# 261105902xxxx-HW-V1_1.net
KiCad netlist of a schematic drawn in EAGLE
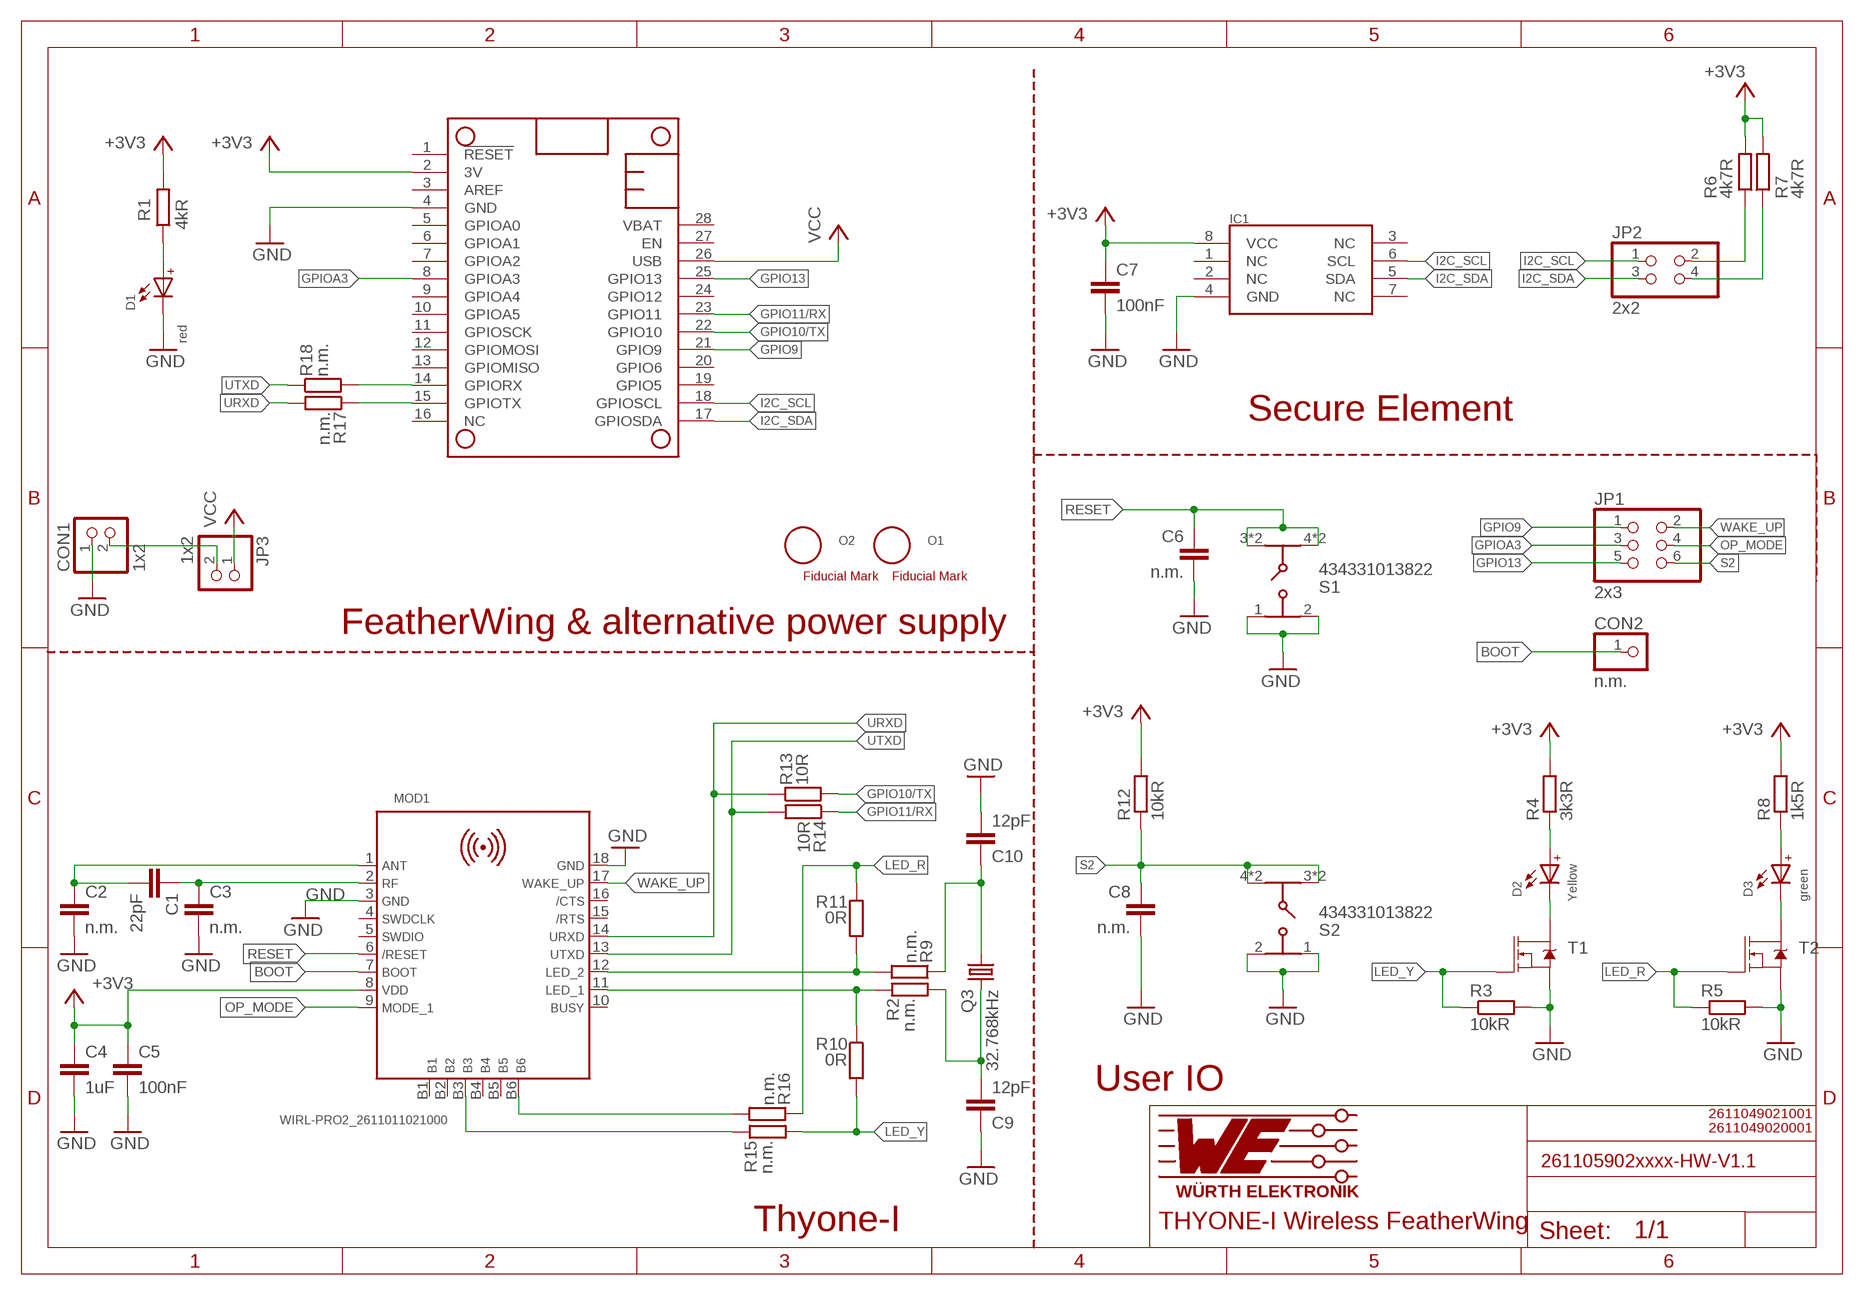
[diagram p0: schematic, sheet 1]

(export (version "E")
  (design (tool "Eeschema 10.0.6"))
  (components
    (comp (ref "C1")
      (value "22pF")
      (footprint "eagle-import:C0402_IPC")
      (fields (field (name "MANUFACTURER") "Samsung"))
      (libsource (lib "eagle-import") (part "rcl-amber_C0402_IPC22PF"))
    )
    (comp (ref "C2")
      (value "n.m.")
      (footprint "eagle-import:C0402_IPC")
      (fields (field (name "MANUFACTURER") "Würth Elektronik"))
      (libsource (lib "eagle-import") (part "C0402_IPC"))
    )
    (comp (ref "C3")
      (value "n.m.")
      (footprint "eagle-import:C0402_IPC")
      (fields (field (name "MANUFACTURER") "Würth Elektronik"))
      (libsource (lib "eagle-import") (part "C0402_IPC"))
    )
    (comp (ref "C4")
      (value "1uF")
      (footprint "eagle-import:C0402_IPC")
      (fields (field (name "MANUFACTURER") "Samsung"))
      (libsource (lib "eagle-import") (part "rcl-amber_C0402_IPC1UF"))
    )
    (comp (ref "C5")
      (value "100nF")
      (footprint "eagle-import:C0402_IPC")
      (fields (field (name "MANUFACTURER") "Yageo"))
      (libsource (lib "eagle-import") (part "rcl-amber_C0402_IPC100NF"))
    )
    (comp (ref "C6")
      (value "n.m.")
      (footprint "eagle-import:C0402_IPC")
      (fields (field (name "MANUFACTURER") "Würth Elektronik"))
      (libsource (lib "eagle-import") (part "C0402_IPC"))
    )
    (comp (ref "C7")
      (value "100nF")
      (footprint "eagle-import:C0402_IPC")
      (fields (field (name "MANUFACTURER") "Yageo"))
      (libsource (lib "eagle-import") (part "rcl-amber_C0402_IPC100NF"))
    )
    (comp (ref "C8")
      (value "n.m.")
      (footprint "eagle-import:C0402_IPC")
      (fields (field (name "MANUFACTURER") "Würth Elektronik"))
      (libsource (lib "eagle-import") (part "C0402_IPC"))
    )
    (comp (ref "C9")
      (value "12pF")
      (footprint "eagle-import:C0402_IPC")
      (fields (field (name "MANUFACTURER") "Yageo"))
      (libsource (lib "eagle-import") (part "C0402_IPC12PF"))
    )
    (comp (ref "C10")
      (value "12pF")
      (footprint "eagle-import:C0402_IPC")
      (fields (field (name "MANUFACTURER") "Yageo"))
      (libsource (lib "eagle-import") (part "C0402_IPC12PF"))
    )
    (comp (ref "CON1")
      (value "1x2")
      (footprint "eagle-import:1X02_R")
      (fields (field (name "MANUFACTURER") "Würth Elektronik"))
      (libsource (lib "eagle-import") (part "PINHD-1X2/R"))
    )
    (comp (ref "CON2")
      (value "n.m.")
      (footprint "eagle-import:1X01_R")
      (libsource (lib "eagle-import") (part "PINHD-1X1/R"))
    )
    (comp (ref "D1")
      (value "red")
      (footprint "eagle-import:WL-SMSW_1204_A")
      (fields (field (name "MANUFACTURER") "Würth Elektronik"))
      (libsource (lib "eagle-import") (part "WL-SMSW_1204_155124VS73200"))
    )
    (comp (ref "D2")
      (value "Yellow")
      (footprint "eagle-import:WL-SMSW_1204_A")
      (fields (field (name "MANUFACTURER") "Würth Elektronik"))
      (libsource (lib "eagle-import") (part "WL-SMSW_1204_155124YS73200"))
    )
    (comp (ref "D3")
      (value "green")
      (footprint "eagle-import:WL-SMSW_1204_A")
      (fields (field (name "MANUFACTURER") "Würth Elektronik"))
      (libsource (lib "eagle-import") (part "WL-SMSW_1204_155124VS73200"))
    )
    (comp (ref "IC1")
      (value "ATECC608A")
      (footprint "eagle-import:SOIC127P600X175-8N")
      (fields (field (name "MANUFACTURER") "microchip"))
      (libsource (lib "eagle-import") (part "ATECC608ASOIC8"))
    )
    (comp (ref "JP1")
      (value "2x3")
      (footprint "eagle-import:2X03")
      (fields (field (name "MANUFACTURER") "Würth Elektronik"))
      (libsource (lib "eagle-import") (part "PINHD-2X3"))
    )
    (comp (ref "JP2")
      (value "2x2")
      (footprint "eagle-import:2X02")
      (fields (field (name "MANUFACTURER") "Würth Elektronik"))
      (libsource (lib "eagle-import") (part "PINHD-2X2"))
    )
    (comp (ref "JP3")
      (value "1x2")
      (footprint "eagle-import:1X02_R")
      (fields (field (name "MANUFACTURER") "Würth Elektronik"))
      (libsource (lib "eagle-import") (part "PINHD-1X2/R"))
    )
    (comp (ref "MOD1")
      (value "WIRL-PRO2_2611011021000")
      (footprint "eagle-import:WIRL-PRO2_2611011021000")
      (fields (field (name "MANUFACTURER") "Würth Elektronik"))
      (libsource (lib "eagle-import") (part "WIRL-PRO2_2611011021000"))
    )
    (comp (ref "MS1")
      (value "header: 1 x 12 & 1 x 16")
      (footprint "eagle-import:FEATHERWING")
      (fields (field (name "COMMENT") "Kit containing 2 headers") (field (name "MANUFACTURER") "Adafruit"))
      (libsource (lib "eagle-import") (part "FEATHERWING"))
    )
    (comp (ref "O1")
      (value "n.m.")
      (footprint "eagle-import:OPTISCHE_MARKE")
      (libsource (lib "eagle-import") (part "OPT_MARKE"))
    )
    (comp (ref "O2")
      (value "n.m.")
      (footprint "eagle-import:OPTISCHE_MARKE")
      (libsource (lib "eagle-import") (part "OPT_MARKE"))
    )
    (comp (ref "Q3")
      (value "32.768kHz")
      (footprint "eagle-import:3216")
      (fields
        (field (name "MANUFACTURER") "Microcrystal")
        (field (name "MANUFACTURER2") "IQD")
        (field (name "NR") "CM7V-T1A-32.768k-9pF-20PPM-TA-QA T3")
        (field (name "NR2") "LFXTAL009706Reel")
      )
      (libsource (lib "eagle-import") (part "3216"))
    )
    (comp (ref "R1")
      (value "4kR")
      (footprint "eagle-import:R0402_IPC")
      (fields (field (name "MANUFACTURER") "Yageo"))
      (libsource (lib "eagle-import") (part "R0402_IPC4K7"))
    )
    (comp (ref "R2")
      (value "n.m.")
      (footprint "eagle-import:R0402_IPC")
      (fields (field (name "MANUFACTURER") "Yageo"))
      (libsource (lib "eagle-import") (part "R0402_IPC"))
    )
    (comp (ref "R3")
      (value "10kR")
      (footprint "eagle-import:R0402_IPC")
      (fields (field (name "MANUFACTURER") "Yageo"))
      (libsource (lib "eagle-import") (part "R0402_IPC10KR"))
    )
    (comp (ref "R4")
      (value "3k3R")
      (footprint "eagle-import:R0402_IPC")
      (fields (field (name "MANUFACTURER") "Yageo"))
      (libsource (lib "eagle-import") (part "R0402_IPC3K3R"))
    )
    (comp (ref "R5")
      (value "10kR")
      (footprint "eagle-import:R0402_IPC")
      (fields (field (name "MANUFACTURER") "Yageo"))
      (libsource (lib "eagle-import") (part "R0402_IPC10KR"))
    )
    (comp (ref "R6")
      (value "4k7R")
      (footprint "eagle-import:R0402_IPC")
      (fields (field (name "MANUFACTURER") "Yageo"))
      (libsource (lib "eagle-import") (part "R0402_IPC4K7"))
    )
    (comp (ref "R7")
      (value "4k7R")
      (footprint "eagle-import:R0402_IPC")
      (fields (field (name "MANUFACTURER") "Yageo"))
      (libsource (lib "eagle-import") (part "R0402_IPC4K7"))
    )
    (comp (ref "R8")
      (value "1k5R")
      (footprint "eagle-import:R0402_IPC")
      (fields (field (name "MANUFACTURER") "Yageo"))
      (libsource (lib "eagle-import") (part "R0402_IPC1K5R"))
    )
    (comp (ref "R9")
      (value "n.m.")
      (footprint "eagle-import:R0402_IPC")
      (fields (field (name "MANUFACTURER") "Yageo"))
      (libsource (lib "eagle-import") (part "R0402_IPC"))
    )
    (comp (ref "R10")
      (value "0R")
      (footprint "eagle-import:R0402_IPC")
      (fields (field (name "MANUFACTURER") "Yageo"))
      (libsource (lib "eagle-import") (part "R0402_IPC0R"))
    )
    (comp (ref "R11")
      (value "0R")
      (footprint "eagle-import:R0402_IPC")
      (fields (field (name "MANUFACTURER") "Yageo"))
      (libsource (lib "eagle-import") (part "R0402_IPC0R"))
    )
    (comp (ref "R12")
      (value "10kR")
      (footprint "eagle-import:R0402_IPC")
      (fields (field (name "MANUFACTURER") "Yageo"))
      (libsource (lib "eagle-import") (part "R0402_IPC10KR"))
    )
    (comp (ref "R13")
      (value "10R")
      (footprint "eagle-import:R0402_IPC")
      (fields (field (name "MANUFACTURER") "Yageo"))
      (libsource (lib "eagle-import") (part "R0402_IPC10R"))
    )
    (comp (ref "R14")
      (value "10R")
      (footprint "eagle-import:R0402_IPC")
      (fields (field (name "MANUFACTURER") "Yageo"))
      (libsource (lib "eagle-import") (part "R0402_IPC10R"))
    )
    (comp (ref "R15")
      (value "n.m.")
      (footprint "eagle-import:R0402_IPC")
      (fields (field (name "MANUFACTURER") "Yageo"))
      (libsource (lib "eagle-import") (part "R0402_IPC"))
    )
    (comp (ref "R16")
      (value "n.m.")
      (footprint "eagle-import:R0402_IPC")
      (fields (field (name "MANUFACTURER") "Yageo"))
      (libsource (lib "eagle-import") (part "R0402_IPC"))
    )
    (comp (ref "R17")
      (value "n.m.")
      (footprint "eagle-import:R0402_IPC")
      (fields (field (name "MANUFACTURER") "Yageo"))
      (libsource (lib "eagle-import") (part "R0402_IPC"))
    )
    (comp (ref "R18")
      (value "n.m.")
      (footprint "eagle-import:R0402_IPC")
      (fields (field (name "MANUFACTURER") "Yageo"))
      (libsource (lib "eagle-import") (part "R0402_IPC"))
    )
    (comp (ref "S1")
      (value "434331013822")
      (footprint "eagle-import:434331013822")
      (fields (field (name "MANUFACTURER") "Würth Elektronik"))
      (libsource (lib "eagle-import") (part "434331013822"))
    )
    (comp (ref "S2")
      (value "434331013822")
      (footprint "eagle-import:434331013822")
      (fields (field (name "MANUFACTURER") "Würth Elektronik"))
      (libsource (lib "eagle-import") (part "434331013822"))
    )
    (comp (ref "T1")
      (value "MOSFET-NCH-BSS138")
      (footprint "eagle-import:SOT23-3")
      (fields (field (name "COMMENT") "220mA/50V/3.5O") (field (name "MANUFACTURER") "Diodes Incorporated"))
      (libsource (lib "eagle-import") (part "MOSFET-NCH-BSS138"))
    )
    (comp (ref "T2")
      (value "MOSFET-NCH-BSS138")
      (footprint "eagle-import:SOT23-3")
      (fields (field (name "COMMENT") "220mA/50V/3.5O") (field (name "MANUFACTURER") "Diodes Incorporated"))
      (libsource (lib "eagle-import") (part "MOSFET-NCH-BSS138"))
    )
  )
  (nets
    (net (code "1") (name "+3V3") (class "Default")
      (node (ref "C4") (pin "1") (pinfunction "1_1") (pintype "passive"))
      (node (ref "C5") (pin "1") (pinfunction "1_1") (pintype "passive"))
      (node (ref "C7") (pin "1") (pinfunction "1_1") (pintype "passive"))
      (node (ref "IC1") (pin "8") (pinfunction "VCC_8") (pintype "bidirectional"))
      (node (ref "MOD1") (pin "8") (pinfunction "VDD_8") (pintype "bidirectional"))
      (node (ref "MS1") (pin "2") (pinfunction "3V_2") (pintype "power_in"))
      (node (ref "R1") (pin "2") (pinfunction "2_2") (pintype "passive"))
      (node (ref "R12") (pin "2") (pinfunction "2_2") (pintype "passive"))
      (node (ref "R4") (pin "2") (pinfunction "2_2") (pintype "passive"))
      (node (ref "R6") (pin "2") (pinfunction "2_2") (pintype "passive"))
      (node (ref "R7") (pin "2") (pinfunction "2_2") (pintype "passive"))
      (node (ref "R8") (pin "2") (pinfunction "2_2") (pintype "passive"))
    )
    (net (code "2") (name "/VBAT") (class "Default")
      (node (ref "MS1") (pin "28") (pinfunction "VBAT_28") (pintype "power_in"))
    )
    (net (code "3") (name "BOOT") (class "Default")
      (node (ref "CON2") (pin "1") (pinfunction "1_1") (pintype "passive"))
      (node (ref "MOD1") (pin "7") (pinfunction "P0.02/BOOT_7") (pintype "bidirectional"))
    )
    (net (code "4") (name "GND") (class "Default")
      (node (ref "C10") (pin "2") (pinfunction "2_2") (pintype "passive"))
      (node (ref "C2") (pin "2") (pinfunction "2_2") (pintype "passive"))
      (node (ref "C3") (pin "2") (pinfunction "2_2") (pintype "passive"))
      (node (ref "C4") (pin "2") (pinfunction "2_2") (pintype "passive"))
      (node (ref "C5") (pin "2") (pinfunction "2_2") (pintype "passive"))
      (node (ref "C6") (pin "2") (pinfunction "2_2") (pintype "passive"))
      (node (ref "C7") (pin "2") (pinfunction "2_2") (pintype "passive"))
      (node (ref "C8") (pin "2") (pinfunction "2_2") (pintype "passive"))
      (node (ref "C9") (pin "1") (pinfunction "1_1") (pintype "passive"))
      (node (ref "CON1") (pin "1") (pinfunction "1_1") (pintype "passive"))
      (node (ref "D1") (pin "1") (pinfunction "-_1") (pintype "passive"))
      (node (ref "IC1") (pin "4") (pinfunction "GND_4") (pintype "bidirectional"))
      (node (ref "MOD1") (pin "18") (pinfunction "GND_18") (pintype "bidirectional"))
      (node (ref "MOD1") (pin "3") (pinfunction "GND_3") (pintype "bidirectional"))
      (node (ref "MS1") (pin "4") (pinfunction "GND_4") (pintype "power_in"))
      (node (ref "R3") (pin "2") (pinfunction "2_2") (pintype "passive"))
      (node (ref "R5") (pin "2") (pinfunction "2_2") (pintype "passive"))
      (node (ref "S1") (pin "1") (pinfunction "1_1") (pintype "passive"))
      (node (ref "S1") (pin "2") (pinfunction "2_2") (pintype "passive"))
      (node (ref "S2") (pin "1") (pinfunction "1_1") (pintype "passive"))
      (node (ref "S2") (pin "2") (pinfunction "2_2") (pintype "passive"))
      (node (ref "T1") (pin "2") (pinfunction "S_2") (pintype "bidirectional"))
      (node (ref "T2") (pin "2") (pinfunction "S_2") (pintype "bidirectional"))
    )
    (net (code "5") (name "GPIO9") (class "Default")
      (node (ref "JP1") (pin "1") (pinfunction "1_1") (pintype "passive"))
      (node (ref "MS1") (pin "21") (pinfunction "GPIO9_21") (pintype "bidirectional"))
    )
    (net (code "6") (name "GPIO10{slash}TX") (class "Default")
      (node (ref "MS1") (pin "22") (pinfunction "GPIO10_22") (pintype "bidirectional"))
      (node (ref "R13") (pin "2") (pinfunction "2_2") (pintype "passive"))
    )
    (net (code "7") (name "GPIO11{slash}RX") (class "Default")
      (node (ref "MS1") (pin "23") (pinfunction "GPIO11_23") (pintype "bidirectional"))
      (node (ref "R14") (pin "1") (pinfunction "1_1") (pintype "passive"))
    )
    (net (code "8") (name "GPIO13") (class "Default")
      (node (ref "JP1") (pin "5") (pinfunction "5_5") (pintype "passive"))
      (node (ref "MS1") (pin "25") (pinfunction "GPIO13_25") (pintype "bidirectional"))
    )
    (net (code "9") (name "GPIOA3") (class "Default")
      (node (ref "JP1") (pin "3") (pinfunction "3_3") (pintype "passive"))
      (node (ref "MS1") (pin "8") (pinfunction "GPIOA3_8") (pintype "bidirectional"))
    )
    (net (code "10") (name "I2C_SCL") (class "Default")
      (node (ref "IC1") (pin "6") (pinfunction "SCL_6") (pintype "bidirectional"))
      (node (ref "JP2") (pin "1") (pinfunction "1_1") (pintype "passive"))
      (node (ref "MS1") (pin "18") (pinfunction "GPIOSCL_18") (pintype "bidirectional"))
    )
    (net (code "11") (name "I2C_SDA") (class "Default")
      (node (ref "IC1") (pin "5") (pinfunction "SDA_5") (pintype "bidirectional"))
      (node (ref "JP2") (pin "3") (pinfunction "3_3") (pintype "passive"))
      (node (ref "MS1") (pin "17") (pinfunction "GPIOSDA_17") (pintype "bidirectional"))
    )
    (net (code "12") (name "LED_R") (class "Default")
      (node (ref "R11") (pin "1") (pinfunction "1_1") (pintype "passive"))
      (node (ref "R16") (pin "1") (pinfunction "1_1") (pintype "passive"))
      (node (ref "R5") (pin "1") (pinfunction "1_1") (pintype "passive"))
      (node (ref "T2") (pin "1") (pinfunction "G_1") (pintype "bidirectional"))
    )
    (net (code "13") (name "LED_Y") (class "Default")
      (node (ref "R10") (pin "2") (pinfunction "2_2") (pintype "passive"))
      (node (ref "R15") (pin "2") (pinfunction "2_2") (pintype "passive"))
      (node (ref "R3") (pin "1") (pinfunction "1_1") (pintype "passive"))
      (node (ref "T1") (pin "1") (pinfunction "G_1") (pintype "bidirectional"))
    )
    (net (code "14") (name "Net-(C9-Pad2)") (class "Default")
      (node (ref "C9") (pin "2") (pinfunction "2_2") (pintype "passive"))
      (node (ref "Q3") (pin "2") (pinfunction "2_2") (pintype "passive"))
      (node (ref "R2") (pin "2") (pinfunction "2_2") (pintype "passive"))
    )
    (net (code "15") (name "Net-(C10-Pad1)") (class "Default")
      (node (ref "C10") (pin "1") (pinfunction "1_1") (pintype "passive"))
      (node (ref "Q3") (pin "1") (pinfunction "1_1") (pintype "passive"))
      (node (ref "R9") (pin "1") (pinfunction "1_1") (pintype "passive"))
    )
    (net (code "16") (name "Net-(CON1-Pad2)") (class "Default")
      (node (ref "CON1") (pin "2") (pinfunction "2_2") (pintype "passive"))
      (node (ref "JP3") (pin "2") (pinfunction "2_2") (pintype "passive"))
    )
    (net (code "17") (name "Net-(D1-+)") (class "Default")
      (node (ref "D1") (pin "2") (pinfunction "+_2") (pintype "passive"))
      (node (ref "R1") (pin "1") (pinfunction "1_1") (pintype "passive"))
    )
    (net (code "18") (name "Net-(D2-+)") (class "Default")
      (node (ref "D2") (pin "2") (pinfunction "+_2") (pintype "passive"))
      (node (ref "R4") (pin "1") (pinfunction "1_1") (pintype "passive"))
    )
    (net (code "19") (name "Net-(D2--)") (class "Default")
      (node (ref "D2") (pin "1") (pinfunction "-_1") (pintype "passive"))
      (node (ref "T1") (pin "3") (pinfunction "D_3") (pintype "bidirectional"))
    )
    (net (code "20") (name "Net-(D3-+)") (class "Default")
      (node (ref "D3") (pin "2") (pinfunction "+_2") (pintype "passive"))
      (node (ref "R8") (pin "1") (pinfunction "1_1") (pintype "passive"))
    )
    (net (code "21") (name "Net-(D3--)") (class "Default")
      (node (ref "D3") (pin "1") (pinfunction "-_1") (pintype "passive"))
      (node (ref "T2") (pin "3") (pinfunction "D_3") (pintype "bidirectional"))
    )
    (net (code "22") (name "Net-(JP2-Pad2)") (class "Default")
      (node (ref "JP2") (pin "2") (pinfunction "2_2") (pintype "passive"))
      (node (ref "R6") (pin "1") (pinfunction "1_1") (pintype "passive"))
    )
    (net (code "23") (name "Net-(JP2-Pad4)") (class "Default")
      (node (ref "JP2") (pin "4") (pinfunction "4_4") (pintype "passive"))
      (node (ref "R7") (pin "1") (pinfunction "1_1") (pintype "passive"))
    )
    (net (code "24") (name "Net-(MOD1-ANT_PAD)") (class "Default")
      (node (ref "C1") (pin "2") (pinfunction "2_2") (pintype "passive"))
      (node (ref "C2") (pin "1") (pinfunction "1_1") (pintype "passive"))
      (node (ref "MOD1") (pin "1") (pinfunction "ANT_PAD_1") (pintype "bidirectional"))
    )
    (net (code "25") (name "Net-(MOD1-P0.00{slash}LED_1)") (class "Default")
      (node (ref "MOD1") (pin "11") (pinfunction "P0.00/LED_1_11") (pintype "bidirectional"))
      (node (ref "R10") (pin "1") (pinfunction "1_1") (pintype "passive"))
      (node (ref "R2") (pin "1") (pinfunction "1_1") (pintype "passive"))
    )
    (net (code "26") (name "Net-(MOD1-P0.01{slash}LED_2)") (class "Default")
      (node (ref "MOD1") (pin "12") (pinfunction "P0.01/LED_2_12") (pintype "bidirectional"))
      (node (ref "R11") (pin "2") (pinfunction "2_2") (pintype "passive"))
      (node (ref "R9") (pin "2") (pinfunction "2_2") (pintype "passive"))
    )
    (net (code "27") (name "Net-(MOD1-PadB3)") (class "Default")
      (node (ref "MOD1") (pin "B3") (pinfunction "B3_B3") (pintype "bidirectional"))
      (node (ref "R15") (pin "1") (pinfunction "1_1") (pintype "passive"))
    )
    (net (code "28") (name "Net-(MOD1-PadB6)") (class "Default")
      (node (ref "MOD1") (pin "B6") (pinfunction "B6_B6") (pintype "bidirectional"))
      (node (ref "R16") (pin "2") (pinfunction "2_2") (pintype "passive"))
    )
    (net (code "29") (name "Net-(MOD1-RF)") (class "Default")
      (node (ref "C1") (pin "1") (pinfunction "1_1") (pintype "passive"))
      (node (ref "C3") (pin "1") (pinfunction "1_1") (pintype "passive"))
      (node (ref "MOD1") (pin "2") (pinfunction "RF_2") (pintype "bidirectional"))
    )
    (net (code "30") (name "Net-(MS1-GPIORX)") (class "Default")
      (node (ref "MS1") (pin "14") (pinfunction "GPIORX_14") (pintype "bidirectional"))
      (node (ref "R18") (pin "2") (pinfunction "2_2") (pintype "passive"))
    )
    (net (code "31") (name "Net-(MS1-GPIOTX)") (class "Default")
      (node (ref "MS1") (pin "15") (pinfunction "GPIOTX_15") (pintype "bidirectional"))
      (node (ref "R17") (pin "1") (pinfunction "1_1") (pintype "passive"))
    )
    (net (code "32") (name "OP_MODE") (class "Default")
      (node (ref "JP1") (pin "4") (pinfunction "4_4") (pintype "passive"))
      (node (ref "MOD1") (pin "9") (pinfunction "P0.19/MODE_1_9") (pintype "bidirectional"))
    )
    (net (code "33") (name "RESET") (class "Default")
      (node (ref "C6") (pin "1") (pinfunction "1_1") (pintype "passive"))
      (node (ref "MOD1") (pin "6") (pinfunction "P0.18/RESET_6") (pintype "bidirectional"))
      (node (ref "S1") (pin "3") (pinfunction "3_3") (pintype "passive"))
      (node (ref "S1") (pin "4") (pinfunction "4_4") (pintype "passive"))
      (node (ref "S1") (pin "5") (pinfunction "3_5") (pintype "passive"))
      (node (ref "S1") (pin "6") (pinfunction "4_6") (pintype "passive"))
    )
    (net (code "34") (name "S2") (class "Default")
      (node (ref "C8") (pin "1") (pinfunction "1_1") (pintype "passive"))
      (node (ref "JP1") (pin "6") (pinfunction "6_6") (pintype "passive"))
      (node (ref "R12") (pin "1") (pinfunction "1_1") (pintype "passive"))
      (node (ref "S2") (pin "3") (pinfunction "3_3") (pintype "passive"))
      (node (ref "S2") (pin "4") (pinfunction "4_4") (pintype "passive"))
      (node (ref "S2") (pin "5") (pinfunction "3_5") (pintype "passive"))
      (node (ref "S2") (pin "6") (pinfunction "4_6") (pintype "passive"))
    )
    (net (code "35") (name "URXD") (class "Default")
      (node (ref "MOD1") (pin "14") (pinfunction "P1.09/URXD_14") (pintype "bidirectional"))
      (node (ref "R13") (pin "1") (pinfunction "1_1") (pintype "passive"))
      (node (ref "R17") (pin "2") (pinfunction "2_2") (pintype "passive"))
    )
    (net (code "36") (name "UTXD") (class "Default")
      (node (ref "MOD1") (pin "13") (pinfunction "P1.08/UTXD_13") (pintype "bidirectional"))
      (node (ref "R14") (pin "2") (pinfunction "2_2") (pintype "passive"))
      (node (ref "R18") (pin "1") (pinfunction "1_1") (pintype "passive"))
    )
    (net (code "37") (name "VCC") (class "Default")
      (node (ref "JP3") (pin "1") (pinfunction "1_1") (pintype "passive"))
      (node (ref "MS1") (pin "26") (pinfunction "USB_26") (pintype "power_in"))
    )
    (net (code "38") (name "WAKE_UP") (class "Default")
      (node (ref "JP1") (pin "2") (pinfunction "2_2") (pintype "passive"))
      (node (ref "MOD1") (pin "17") (pinfunction "P0.03/WAKE_UP_17") (pintype "bidirectional"))
    )
    (net (code "39") (name "unconnected-(IC1-NC-Pad1)") (class "Default")
      (node (ref "IC1") (pin "1") (pinfunction "NC_1") (pintype "bidirectional"))
    )
    (net (code "40") (name "unconnected-(IC1-NC-Pad2)") (class "Default")
      (node (ref "IC1") (pin "2") (pinfunction "NC_2") (pintype "bidirectional"))
    )
    (net (code "41") (name "unconnected-(IC1-NC-Pad3)") (class "Default")
      (node (ref "IC1") (pin "3") (pinfunction "NC_3") (pintype "bidirectional"))
    )
    (net (code "42") (name "unconnected-(IC1-NC-Pad7)") (class "Default")
      (node (ref "IC1") (pin "7") (pinfunction "NC_7") (pintype "bidirectional"))
    )
    (net (code "43") (name "unconnected-(MOD1-P0.11{slash}~{RTS}-Pad15)") (class "Default")
      (node (ref "MOD1") (pin "15") (pinfunction "P0.11/~{RTS}_15") (pintype "bidirectional"))
    )
    (net (code "44") (name "unconnected-(MOD1-P0.12{slash}~{CTS}-Pad16)") (class "Default")
      (node (ref "MOD1") (pin "16") (pinfunction "P0.12/~{CTS}_16") (pintype "bidirectional"))
    )
    (net (code "45") (name "unconnected-(MOD1-P0.22{slash}BUSY-Pad10)") (class "Default")
      (node (ref "MOD1") (pin "10") (pinfunction "P0.22/BUSY_10") (pintype "bidirectional"))
    )
    (net (code "46") (name "unconnected-(MOD1-PadB1)") (class "Default")
      (node (ref "MOD1") (pin "B1") (pinfunction "B1_B1") (pintype "bidirectional"))
    )
    (net (code "47") (name "unconnected-(MOD1-PadB2)") (class "Default")
      (node (ref "MOD1") (pin "B2") (pinfunction "B2_B2") (pintype "bidirectional"))
    )
    (net (code "48") (name "unconnected-(MOD1-PadB4)") (class "Default")
      (node (ref "MOD1") (pin "B4") (pinfunction "B4_B4") (pintype "bidirectional"))
    )
    (net (code "49") (name "unconnected-(MOD1-PadB5)") (class "Default")
      (node (ref "MOD1") (pin "B5") (pinfunction "B5_B5") (pintype "bidirectional"))
    )
    (net (code "50") (name "unconnected-(MOD1-SWDCLK-Pad4)") (class "Default")
      (node (ref "MOD1") (pin "4") (pinfunction "SWDCLK_4") (pintype "bidirectional"))
    )
    (net (code "51") (name "unconnected-(MOD1-SWDIO-Pad5)") (class "Default")
      (node (ref "MOD1") (pin "5") (pinfunction "SWDIO_5") (pintype "bidirectional"))
    )
    (net (code "52") (name "unconnected-(MS1-AREF-Pad3)") (class "Default")
      (node (ref "MS1") (pin "3") (pinfunction "AREF_3") (pintype "passive"))
    )
    (net (code "53") (name "unconnected-(MS1-EN-Pad27)") (class "Default")
      (node (ref "MS1") (pin "27") (pinfunction "EN_27") (pintype "passive"))
    )
    (net (code "54") (name "unconnected-(MS1-GPIO5-Pad19)") (class "Default")
      (node (ref "MS1") (pin "19") (pinfunction "GPIO5_19") (pintype "bidirectional"))
    )
    (net (code "55") (name "unconnected-(MS1-GPIO6-Pad20)") (class "Default")
      (node (ref "MS1") (pin "20") (pinfunction "GPIO6_20") (pintype "bidirectional"))
    )
    (net (code "56") (name "unconnected-(MS1-GPIO12-Pad24)") (class "Default")
      (node (ref "MS1") (pin "24") (pinfunction "GPIO12_24") (pintype "bidirectional"))
    )
    (net (code "57") (name "unconnected-(MS1-GPIOA0-Pad5)") (class "Default")
      (node (ref "MS1") (pin "5") (pinfunction "GPIOA0_5") (pintype "bidirectional"))
    )
    (net (code "58") (name "unconnected-(MS1-GPIOA1-Pad6)") (class "Default")
      (node (ref "MS1") (pin "6") (pinfunction "GPIOA1_6") (pintype "bidirectional"))
    )
    (net (code "59") (name "unconnected-(MS1-GPIOA2-Pad7)") (class "Default")
      (node (ref "MS1") (pin "7") (pinfunction "GPIOA2_7") (pintype "bidirectional"))
    )
    (net (code "60") (name "unconnected-(MS1-GPIOA4-Pad9)") (class "Default")
      (node (ref "MS1") (pin "9") (pinfunction "GPIOA4_9") (pintype "bidirectional"))
    )
    (net (code "61") (name "unconnected-(MS1-GPIOA5-Pad10)") (class "Default")
      (node (ref "MS1") (pin "10") (pinfunction "GPIOA5_10") (pintype "bidirectional"))
    )
    (net (code "62") (name "unconnected-(MS1-GPIOMISO-Pad13)") (class "Default")
      (node (ref "MS1") (pin "13") (pinfunction "GPIOMISO_13") (pintype "bidirectional"))
    )
    (net (code "63") (name "unconnected-(MS1-GPIOMOSI-Pad12)") (class "Default")
      (node (ref "MS1") (pin "12") (pinfunction "GPIOMOSI_12") (pintype "bidirectional"))
    )
    (net (code "64") (name "unconnected-(MS1-GPIOSCK-Pad11)") (class "Default")
      (node (ref "MS1") (pin "11") (pinfunction "GPIOSCK_11") (pintype "bidirectional"))
    )
    (net (code "65") (name "unconnected-(MS1-NC-Pad16)") (class "Default")
      (node (ref "MS1") (pin "16") (pinfunction "NC_16") (pintype "passive"))
    )
    (net (code "66") (name "unconnected-(MS1-~{RESET}-Pad1)") (class "Default")
      (node (ref "MS1") (pin "1") (pinfunction "~{RESET}_1") (pintype "input"))
    )
  )
)
